# RPL_POWER.net
KiCad netlist of a schematic drawn in Altium Designer
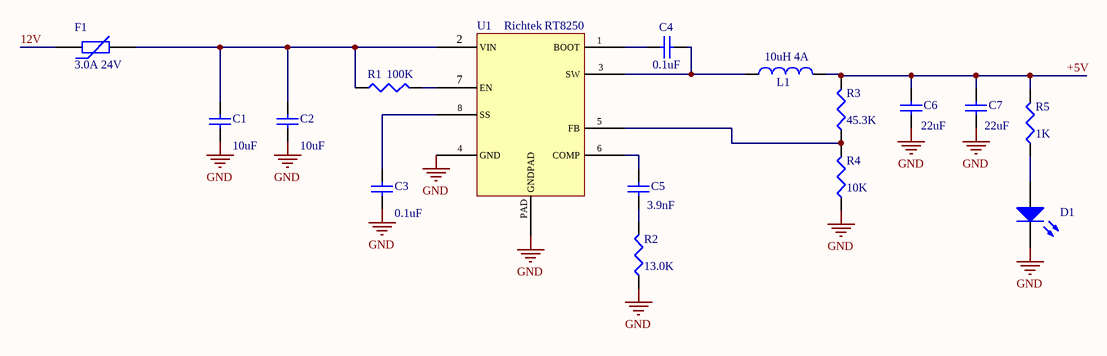
[diagram p0: RPL_POWER.SchDoc]

(export (version "E")
  (design (tool "Eeschema 10.0.6"))
  (components
    (comp (ref "C1")
      (value "10uF")
      (footprint "C1206")
      (description "Capacitor (Semiconductor SIM Model)")
      (fields (field (name "Comment") "Cap Semi") (field (name "PUBLISHER") "Altium Limited"))
      (libsource (lib "Miscellaneous Devices") (part "Cap Semi"))
    )
    (comp (ref "C2")
      (value "10uF")
      (footprint "C1206")
      (description "Capacitor (Semiconductor SIM Model)")
      (fields (field (name "Comment") "Cap Semi") (field (name "PUBLISHER") "Altium Limited"))
      (libsource (lib "Miscellaneous Devices") (part "Cap Semi"))
    )
    (comp (ref "C3")
      (value "0.1uF")
      (footprint "C1206")
      (description "Capacitor (Semiconductor SIM Model)")
      (fields (field (name "Comment") "Cap Semi") (field (name "PUBLISHER") "Altium Limited"))
      (libsource (lib "Miscellaneous Devices") (part "Cap Semi"))
    )
    (comp (ref "C4")
      (value "0.1uF")
      (footprint "C1206")
      (description "Capacitor (Semiconductor SIM Model)")
      (fields (field (name "Comment") "Cap Semi") (field (name "PUBLISHER") "Altium Limited"))
      (libsource (lib "Miscellaneous Devices") (part "Cap Semi"))
    )
    (comp (ref "C5")
      (value "3.9nF")
      (footprint "C1206")
      (description "Capacitor (Semiconductor SIM Model)")
      (fields (field (name "Comment") "Cap Semi") (field (name "PUBLISHER") "Altium Limited"))
      (libsource (lib "Miscellaneous Devices") (part "Cap Semi"))
    )
    (comp (ref "C6")
      (value "22uF")
      (footprint "C1206")
      (description "Capacitor (Semiconductor SIM Model)")
      (fields (field (name "Comment") "Cap Semi") (field (name "PUBLISHER") "Altium Limited"))
      (libsource (lib "Miscellaneous Devices") (part "Cap Semi"))
    )
    (comp (ref "C7")
      (value "22uF")
      (footprint "C1206")
      (description "Capacitor (Semiconductor SIM Model)")
      (fields (field (name "Comment") "Cap Semi") (field (name "PUBLISHER") "Altium Limited"))
      (libsource (lib "Miscellaneous Devices") (part "Cap Semi"))
    )
    (comp (ref "D1")
      (value "LED2")
      (footprint "3.2X1.6X1.1")
      (description "Typical RED, GREEN, YELLOW, AMBER GaAs LED")
      (fields (field (name "PUBLISHER") "Altium Limited"))
      (libsource (lib "Miscellaneous Devices") (part "LED2"))
    )
    (comp (ref "F1")
      (value "3.0A 24V")
      (footprint "6-0805_N")
      (description "Varistor (Voltage-Sensitive Resistor)")
      (fields (field (name "PUBLISHER") "Altium Limited"))
      (libsource (lib "Miscellaneous Devices") (part "Res Varistor"))
    )
    (comp (ref "L1")
      (value "10uH 4A")
      (footprint "0402-A")
      (description "Inductor")
      (fields (field (name "PUBLISHER") "Altium Limited"))
      (libsource (lib "Miscellaneous Devices") (part "Inductor"))
    )
    (comp (ref "R1")
      (value "100K")
      (footprint "J1-0603")
      (description "Resistor")
      (fields (field (name "Comment") "Res3") (field (name "PUBLISHER") "Altium Limited"))
      (libsource (lib "Miscellaneous Devices") (part "Res3"))
    )
    (comp (ref "R2")
      (value "13.0K")
      (footprint "J1-0603")
      (description "Resistor")
      (fields (field (name "Comment") "Res3") (field (name "PUBLISHER") "Altium Limited"))
      (libsource (lib "Miscellaneous Devices") (part "Res3"))
    )
    (comp (ref "R3")
      (value "45.3K")
      (footprint "J1-0603")
      (description "Resistor")
      (fields (field (name "Comment") "Res3") (field (name "PUBLISHER") "Altium Limited"))
      (libsource (lib "Miscellaneous Devices") (part "Res3"))
    )
    (comp (ref "R4")
      (value "10K")
      (footprint "J1-0603")
      (description "Resistor")
      (fields (field (name "Comment") "Res3") (field (name "PUBLISHER") "Altium Limited"))
      (libsource (lib "Miscellaneous Devices") (part "Res3"))
    )
    (comp (ref "R5")
      (value "1K")
      (footprint "J1-0603")
      (description "Resistor")
      (fields (field (name "Comment") "Res3") (field (name "PUBLISHER") "Altium Limited"))
      (libsource (lib "Miscellaneous Devices") (part "Res3"))
    )
    (comp (ref "U1")
      (value "RT8250GSP")
      (fields (field (name "MANUFACTURER") "Richtek") (field (name "MANUFACTURER PART NUMBER") "RT8250"))
      (libsource (lib "Richtek RT8250") (part "RT8250"))
    )
  )
  (nets
    (net (code "1") (name "/+5V") (class "Default")
      (node (ref "C6") (pin "2") (pinfunction "2_2") (pintype "passive"))
      (node (ref "C7") (pin "2") (pinfunction "2_2") (pintype "passive"))
      (node (ref "L1") (pin "2") (pinfunction "2_2") (pintype "passive"))
      (node (ref "R3") (pin "2") (pinfunction "2_2") (pintype "passive"))
      (node (ref "R5") (pin "2") (pinfunction "2_2") (pintype "passive"))
    )
    (net (code "2") (name "/12V") (class "Default")
      (node (ref "F1") (pin "1") (pinfunction "1_1") (pintype "passive"))
    )
    (net (code "3") (name "GND") (class "Default")
      (node (ref "C1") (pin "1") (pinfunction "1_1") (pintype "passive"))
      (node (ref "C2") (pin "1") (pinfunction "1_1") (pintype "passive"))
      (node (ref "C3") (pin "1") (pinfunction "1_1") (pintype "passive"))
      (node (ref "C6") (pin "1") (pinfunction "1_1") (pintype "passive"))
      (node (ref "C7") (pin "1") (pinfunction "1_1") (pintype "passive"))
      (node (ref "D1") (pin "2") (pinfunction "K_2") (pintype "passive"))
      (node (ref "R2") (pin "1") (pinfunction "1_1") (pintype "passive"))
      (node (ref "R4") (pin "1") (pinfunction "1_1") (pintype "passive"))
      (node (ref "U1") (pin "4") (pinfunction "GND_4") (pintype "power_in"))
      (node (ref "U1") (pin "PAD") (pinfunction "GNDPAD_PAD") (pintype "passive"))
    )
    (net (code "4") (name "Net-(C5-Pad1)") (class "Default")
      (node (ref "C5") (pin "1") (pinfunction "1_1") (pintype "passive"))
      (node (ref "R2") (pin "2") (pinfunction "2_2") (pintype "passive"))
    )
    (net (code "5") (name "Net-(D1-A)") (class "Default")
      (node (ref "D1") (pin "1") (pinfunction "A_1") (pintype "passive"))
      (node (ref "R5") (pin "1") (pinfunction "1_1") (pintype "passive"))
    )
    (net (code "6") (name "Net-(U1-BOOT)") (class "Default")
      (node (ref "C4") (pin "1") (pinfunction "1_1") (pintype "passive"))
      (node (ref "U1") (pin "1") (pinfunction "BOOT_1") (pintype "passive"))
    )
    (net (code "7") (name "Net-(U1-COMP)") (class "Default")
      (node (ref "C5") (pin "2") (pinfunction "2_2") (pintype "passive"))
      (node (ref "U1") (pin "6") (pinfunction "COMP_6") (pintype "passive"))
    )
    (net (code "8") (name "Net-(U1-EN)") (class "Default")
      (node (ref "R1") (pin "2") (pinfunction "2_2") (pintype "passive"))
      (node (ref "U1") (pin "7") (pinfunction "EN_7") (pintype "passive"))
    )
    (net (code "9") (name "Net-(U1-FB)") (class "Default")
      (node (ref "R3") (pin "1") (pinfunction "1_1") (pintype "passive"))
      (node (ref "R4") (pin "2") (pinfunction "2_2") (pintype "passive"))
      (node (ref "U1") (pin "5") (pinfunction "FB_5") (pintype "passive"))
    )
    (net (code "10") (name "Net-(U1-SS)") (class "Default")
      (node (ref "C3") (pin "2") (pinfunction "2_2") (pintype "passive"))
      (node (ref "U1") (pin "8") (pinfunction "SS_8") (pintype "passive"))
    )
    (net (code "11") (name "Net-(U1-SW)") (class "Default")
      (node (ref "C4") (pin "2") (pinfunction "2_2") (pintype "passive"))
      (node (ref "L1") (pin "1") (pinfunction "1_1") (pintype "passive"))
      (node (ref "U1") (pin "3") (pinfunction "SW_3") (pintype "passive"))
    )
    (net (code "12") (name "Net-(U1-VIN)") (class "Default")
      (node (ref "C1") (pin "2") (pinfunction "2_2") (pintype "passive"))
      (node (ref "C2") (pin "2") (pinfunction "2_2") (pintype "passive"))
      (node (ref "F1") (pin "2") (pinfunction "2_2") (pintype "passive"))
      (node (ref "R1") (pin "1") (pinfunction "1_1") (pintype "passive"))
      (node (ref "U1") (pin "2") (pinfunction "VIN_2") (pintype "power_in"))
    )
  )
)
